# Powerboard_Conector_2.net
KiCad netlist of a schematic drawn in Altium Designer
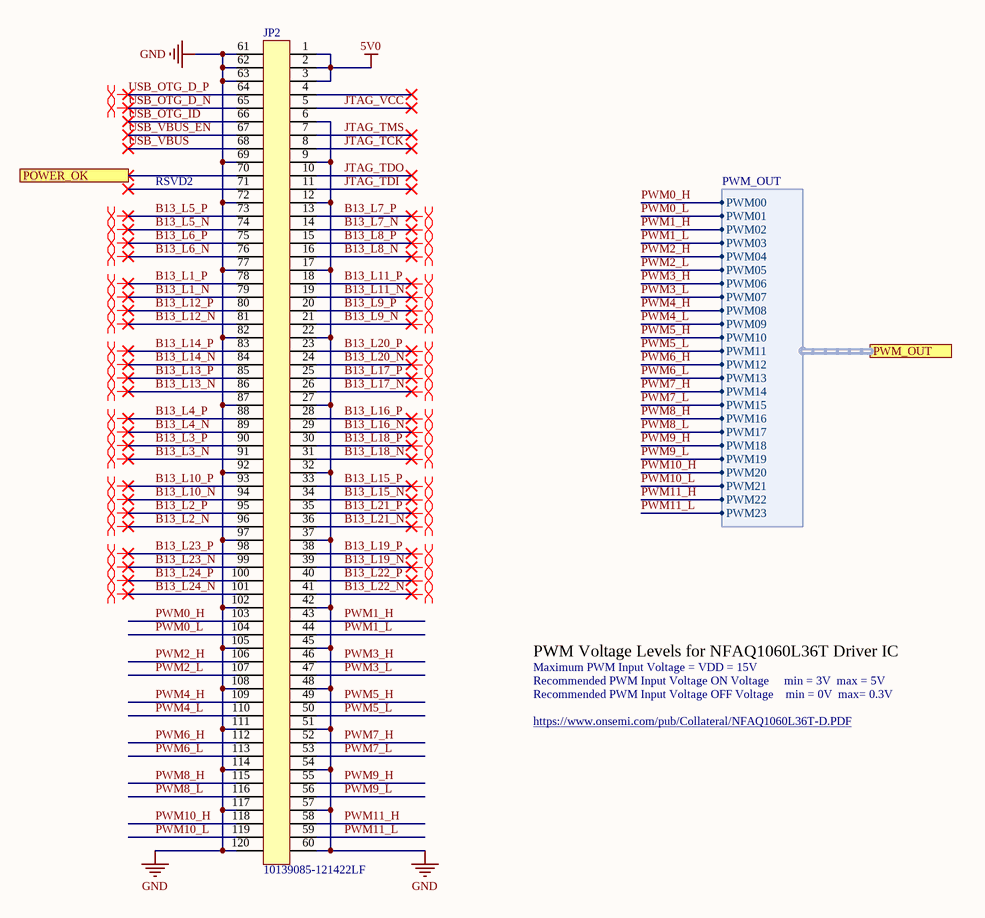
[diagram p0: Powerboard_Conector_2.SchDoc]

(export (version "E")
  (design (tool "Eeschema 10.0.6"))
  (components
    (comp (ref "JP2")
      (value "10139085-121422LF")
      (footprint "10139085-121422LF")
      (description "Bergstack+ 0.8mm pich - 120pin B2B connector")
      (fields (field (name "PUBLISHER") "Amphenol ICC"))
      (libsource (lib "connectors_testpoints") (part "10139085-121422LF"))
    )
  )
  (nets
    (net (code "2") (name "/B13_L1_N") (class "Default")
      (node (ref "JP2") (pin "79") (pintype "passive+no_connect"))
    )
    (net (code "3") (name "/B13_L1_P") (class "Default")
      (node (ref "JP2") (pin "78") (pintype "passive+no_connect"))
    )
    (net (code "4") (name "/B13_L2_N") (class "Default")
      (node (ref "JP2") (pin "96") (pintype "passive+no_connect"))
    )
    (net (code "5") (name "/B13_L2_P") (class "Default")
      (node (ref "JP2") (pin "95") (pintype "passive+no_connect"))
    )
    (net (code "6") (name "/B13_L3_N") (class "Default")
      (node (ref "JP2") (pin "91") (pintype "passive+no_connect"))
    )
    (net (code "7") (name "/B13_L3_P") (class "Default")
      (node (ref "JP2") (pin "90") (pintype "passive+no_connect"))
    )
    (net (code "8") (name "/B13_L4_N") (class "Default")
      (node (ref "JP2") (pin "89") (pintype "passive+no_connect"))
    )
    (net (code "9") (name "/B13_L4_P") (class "Default")
      (node (ref "JP2") (pin "88") (pintype "passive+no_connect"))
    )
    (net (code "10") (name "/B13_L5_N") (class "Default")
      (node (ref "JP2") (pin "74") (pintype "passive+no_connect"))
    )
    (net (code "11") (name "/B13_L5_P") (class "Default")
      (node (ref "JP2") (pin "73") (pintype "passive+no_connect"))
    )
    (net (code "12") (name "/B13_L6_N") (class "Default")
      (node (ref "JP2") (pin "76") (pintype "passive+no_connect"))
    )
    (net (code "13") (name "/B13_L6_P") (class "Default")
      (node (ref "JP2") (pin "75") (pintype "passive+no_connect"))
    )
    (net (code "14") (name "/B13_L7_N") (class "Default")
      (node (ref "JP2") (pin "14") (pintype "passive+no_connect"))
    )
    (net (code "15") (name "/B13_L7_P") (class "Default")
      (node (ref "JP2") (pin "13") (pintype "passive+no_connect"))
    )
    (net (code "16") (name "/B13_L8_N") (class "Default")
      (node (ref "JP2") (pin "16") (pintype "passive+no_connect"))
    )
    (net (code "17") (name "/B13_L8_P") (class "Default")
      (node (ref "JP2") (pin "15") (pintype "passive+no_connect"))
    )
    (net (code "18") (name "/B13_L9_N") (class "Default")
      (node (ref "JP2") (pin "21") (pintype "passive+no_connect"))
    )
    (net (code "19") (name "/B13_L9_P") (class "Default")
      (node (ref "JP2") (pin "20") (pintype "passive+no_connect"))
    )
    (net (code "20") (name "/B13_L10_N") (class "Default")
      (node (ref "JP2") (pin "94") (pintype "passive+no_connect"))
    )
    (net (code "21") (name "/B13_L10_P") (class "Default")
      (node (ref "JP2") (pin "93") (pintype "passive+no_connect"))
    )
    (net (code "22") (name "/B13_L11_N") (class "Default")
      (node (ref "JP2") (pin "19") (pintype "passive+no_connect"))
    )
    (net (code "23") (name "/B13_L11_P") (class "Default")
      (node (ref "JP2") (pin "18") (pintype "passive+no_connect"))
    )
    (net (code "24") (name "/B13_L12_N") (class "Default")
      (node (ref "JP2") (pin "81") (pintype "passive+no_connect"))
    )
    (net (code "25") (name "/B13_L12_P") (class "Default")
      (node (ref "JP2") (pin "80") (pintype "passive+no_connect"))
    )
    (net (code "26") (name "/B13_L13_N") (class "Default")
      (node (ref "JP2") (pin "86") (pintype "passive+no_connect"))
    )
    (net (code "27") (name "/B13_L13_P") (class "Default")
      (node (ref "JP2") (pin "85") (pintype "passive+no_connect"))
    )
    (net (code "28") (name "/B13_L14_N") (class "Default")
      (node (ref "JP2") (pin "84") (pintype "passive+no_connect"))
    )
    (net (code "29") (name "/B13_L14_P") (class "Default")
      (node (ref "JP2") (pin "83") (pintype "passive+no_connect"))
    )
    (net (code "30") (name "/B13_L15_N") (class "Default")
      (node (ref "JP2") (pin "34") (pintype "passive+no_connect"))
    )
    (net (code "31") (name "/B13_L15_P") (class "Default")
      (node (ref "JP2") (pin "33") (pintype "passive+no_connect"))
    )
    (net (code "32") (name "/B13_L16_N") (class "Default")
      (node (ref "JP2") (pin "29") (pintype "passive+no_connect"))
    )
    (net (code "33") (name "/B13_L16_P") (class "Default")
      (node (ref "JP2") (pin "28") (pintype "passive+no_connect"))
    )
    (net (code "34") (name "/B13_L17_N") (class "Default")
      (node (ref "JP2") (pin "26") (pintype "passive+no_connect"))
    )
    (net (code "35") (name "/B13_L17_P") (class "Default")
      (node (ref "JP2") (pin "25") (pintype "passive+no_connect"))
    )
    (net (code "36") (name "/B13_L18_N") (class "Default")
      (node (ref "JP2") (pin "31") (pintype "passive+no_connect"))
    )
    (net (code "37") (name "/B13_L18_P") (class "Default")
      (node (ref "JP2") (pin "30") (pintype "passive+no_connect"))
    )
    (net (code "38") (name "/B13_L19_N") (class "Default")
      (node (ref "JP2") (pin "39") (pintype "passive+no_connect"))
    )
    (net (code "39") (name "/B13_L19_P") (class "Default")
      (node (ref "JP2") (pin "38") (pintype "passive+no_connect"))
    )
    (net (code "40") (name "/B13_L20_N") (class "Default")
      (node (ref "JP2") (pin "24") (pintype "passive+no_connect"))
    )
    (net (code "41") (name "/B13_L20_P") (class "Default")
      (node (ref "JP2") (pin "23") (pintype "passive+no_connect"))
    )
    (net (code "42") (name "/B13_L21_N") (class "Default")
      (node (ref "JP2") (pin "36") (pintype "passive+no_connect"))
    )
    (net (code "43") (name "/B13_L21_P") (class "Default")
      (node (ref "JP2") (pin "35") (pintype "passive+no_connect"))
    )
    (net (code "44") (name "/B13_L22_N") (class "Default")
      (node (ref "JP2") (pin "41") (pintype "passive+no_connect"))
    )
    (net (code "45") (name "/B13_L22_P") (class "Default")
      (node (ref "JP2") (pin "40") (pintype "passive+no_connect"))
    )
    (net (code "46") (name "/B13_L23_N") (class "Default")
      (node (ref "JP2") (pin "99") (pintype "passive+no_connect"))
    )
    (net (code "47") (name "/B13_L23_P") (class "Default")
      (node (ref "JP2") (pin "98") (pintype "passive+no_connect"))
    )
    (net (code "48") (name "/B13_L24_N") (class "Default")
      (node (ref "JP2") (pin "101") (pintype "passive+no_connect"))
    )
    (net (code "49") (name "/B13_L24_P") (class "Default")
      (node (ref "JP2") (pin "100") (pintype "passive+no_connect"))
    )
    (net (code "50") (name "/JTAG_TCK") (class "Default")
      (node (ref "JP2") (pin "8") (pintype "passive+no_connect"))
    )
    (net (code "51") (name "/JTAG_TDI") (class "Default")
      (node (ref "JP2") (pin "11") (pintype "passive+no_connect"))
    )
    (net (code "52") (name "/JTAG_TDO") (class "Default")
      (node (ref "JP2") (pin "10") (pintype "passive+no_connect"))
    )
    (net (code "53") (name "/JTAG_TMS") (class "Default")
      (node (ref "JP2") (pin "7") (pintype "passive+no_connect"))
    )
    (net (code "54") (name "/JTAG_VCC") (class "Default")
      (node (ref "JP2") (pin "5") (pintype "passive+no_connect"))
    )
    (net (code "55") (name "/POWER_OK") (class "Default")
      (node (ref "JP2") (pin "70") (pintype "passive+no_connect"))
    )
    (net (code "56") (name "/PWM0_H") (class "Default") (node (ref "JP2") (pin "103") (pintype "passive")))
    (net (code "57") (name "/PWM0_L") (class "Default") (node (ref "JP2") (pin "104") (pintype "passive")))
    (net (code "58") (name "/PWM1_H") (class "Default") (node (ref "JP2") (pin "43") (pintype "passive")))
    (net (code "59") (name "/PWM1_L") (class "Default") (node (ref "JP2") (pin "44") (pintype "passive")))
    (net (code "60") (name "/PWM2_H") (class "Default") (node (ref "JP2") (pin "106") (pintype "passive")))
    (net (code "61") (name "/PWM2_L") (class "Default") (node (ref "JP2") (pin "107") (pintype "passive")))
    (net (code "62") (name "/PWM3_H") (class "Default") (node (ref "JP2") (pin "46") (pintype "passive")))
    (net (code "63") (name "/PWM3_L") (class "Default") (node (ref "JP2") (pin "47") (pintype "passive")))
    (net (code "64") (name "/PWM4_H") (class "Default") (node (ref "JP2") (pin "109") (pintype "passive")))
    (net (code "65") (name "/PWM4_L") (class "Default") (node (ref "JP2") (pin "110") (pintype "passive")))
    (net (code "66") (name "/PWM5_H") (class "Default") (node (ref "JP2") (pin "49") (pintype "passive")))
    (net (code "67") (name "/PWM5_L") (class "Default") (node (ref "JP2") (pin "50") (pintype "passive")))
    (net (code "68") (name "/PWM6_H") (class "Default") (node (ref "JP2") (pin "112") (pintype "passive")))
    (net (code "69") (name "/PWM6_L") (class "Default") (node (ref "JP2") (pin "113") (pintype "passive")))
    (net (code "70") (name "/PWM7_H") (class "Default") (node (ref "JP2") (pin "52") (pintype "passive")))
    (net (code "71") (name "/PWM7_L") (class "Default") (node (ref "JP2") (pin "53") (pintype "passive")))
    (net (code "72") (name "/PWM8_H") (class "Default") (node (ref "JP2") (pin "115") (pintype "passive")))
    (net (code "73") (name "/PWM8_L") (class "Default") (node (ref "JP2") (pin "116") (pintype "passive")))
    (net (code "74") (name "/PWM9_H") (class "Default") (node (ref "JP2") (pin "55") (pintype "passive")))
    (net (code "75") (name "/PWM9_L") (class "Default") (node (ref "JP2") (pin "56") (pintype "passive")))
    (net (code "76") (name "/PWM10_H") (class "Default") (node (ref "JP2") (pin "118") (pintype "passive")))
    (net (code "77") (name "/PWM10_L") (class "Default") (node (ref "JP2") (pin "119") (pintype "passive")))
    (net (code "78") (name "/PWM11_H") (class "Default") (node (ref "JP2") (pin "58") (pintype "passive")))
    (net (code "79") (name "/PWM11_L") (class "Default") (node (ref "JP2") (pin "59") (pintype "passive")))
    (net (code "80") (name "/USB_OTG_D_N") (class "Default")
      (node (ref "JP2") (pin "65") (pintype "passive+no_connect"))
    )
    (net (code "81") (name "/USB_OTG_D_P") (class "Default")
      (node (ref "JP2") (pin "64") (pintype "passive+no_connect"))
    )
    (net (code "82") (name "/USB_OTG_ID") (class "Default")
      (node (ref "JP2") (pin "66") (pintype "passive+no_connect"))
    )
    (net (code "83") (name "/USB_VBUS") (class "Default")
      (node (ref "JP2") (pin "68") (pintype "passive+no_connect"))
    )
    (net (code "84") (name "/USB_VBUS_EN") (class "Default")
      (node (ref "JP2") (pin "67") (pintype "passive+no_connect"))
    )
    (net (code "86") (name "5V0") (class "Default")
      (node (ref "JP2") (pin "1") (pintype "passive"))
      (node (ref "JP2") (pin "2") (pintype "passive"))
      (node (ref "JP2") (pin "3") (pintype "passive"))
    )
    (net (code "87") (name "GND") (class "Default")
      (node (ref "JP2") (pin "102") (pintype "passive"))
      (node (ref "JP2") (pin "105") (pintype "passive"))
      (node (ref "JP2") (pin "108") (pintype "passive"))
      (node (ref "JP2") (pin "111") (pintype "passive"))
      (node (ref "JP2") (pin "114") (pintype "passive"))
      (node (ref "JP2") (pin "117") (pintype "passive"))
      (node (ref "JP2") (pin "12") (pintype "passive"))
      (node (ref "JP2") (pin "120") (pintype "passive"))
      (node (ref "JP2") (pin "17") (pintype "passive"))
      (node (ref "JP2") (pin "22") (pintype "passive"))
      (node (ref "JP2") (pin "27") (pintype "passive"))
      (node (ref "JP2") (pin "32") (pintype "passive"))
      (node (ref "JP2") (pin "37") (pintype "passive"))
      (node (ref "JP2") (pin "42") (pintype "passive"))
      (node (ref "JP2") (pin "45") (pintype "passive"))
      (node (ref "JP2") (pin "48") (pintype "passive"))
      (node (ref "JP2") (pin "51") (pintype "passive"))
      (node (ref "JP2") (pin "54") (pintype "passive"))
      (node (ref "JP2") (pin "57") (pintype "passive"))
      (node (ref "JP2") (pin "6") (pintype "passive"))
      (node (ref "JP2") (pin "60") (pintype "passive"))
      (node (ref "JP2") (pin "61") (pintype "passive"))
      (node (ref "JP2") (pin "62") (pintype "passive"))
      (node (ref "JP2") (pin "63") (pintype "passive"))
      (node (ref "JP2") (pin "69") (pintype "passive"))
      (node (ref "JP2") (pin "72") (pintype "passive"))
      (node (ref "JP2") (pin "77") (pintype "passive"))
      (node (ref "JP2") (pin "82") (pintype "passive"))
      (node (ref "JP2") (pin "87") (pintype "passive"))
      (node (ref "JP2") (pin "9") (pintype "passive"))
      (node (ref "JP2") (pin "92") (pintype "passive"))
      (node (ref "JP2") (pin "97") (pintype "passive"))
    )
    (net (code "88") (name "unconnected-(JP2-Pad4)") (class "Default")
      (node (ref "JP2") (pin "4") (pintype "passive+no_connect"))
    )
    (net (code "89") (name "unconnected-(JP2-Pad71)") (class "Default")
      (node (ref "JP2") (pin "71") (pintype "passive+no_connect"))
    )
  )
)
